# DC24V.net
KiCad netlist of a schematic drawn in Altium Designer
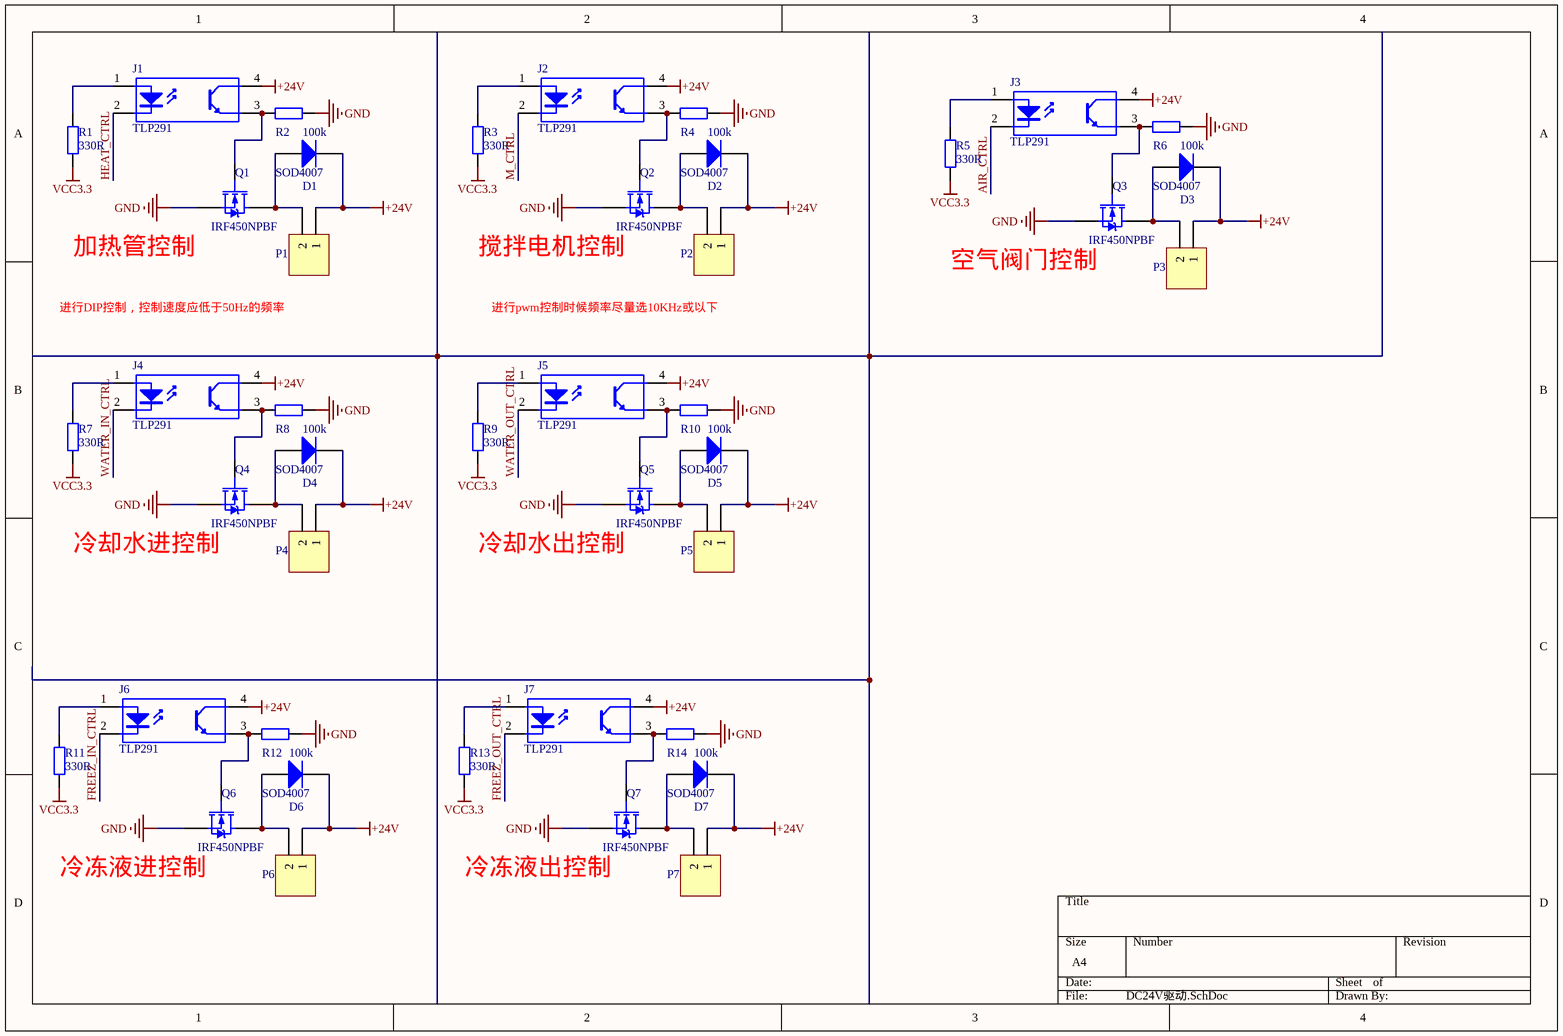
[diagram p0: DC24V驱动.SchDoc]

(export (version "E")
  (design (tool "Eeschema 10.0.6"))
  (components
    (comp (ref "D1")
      (value "Diode")
      (footprint "SOD123")
      (description "二极管")
      (fields (field (name "TYPE") "SOD4007") (field (name "PUBLISHER") "Altium Limited"))
      (libsource (lib "Fszhang") (part "Diode"))
    )
    (comp (ref "D2")
      (value "Diode")
      (footprint "SOD123")
      (description "二极管")
      (fields (field (name "TYPE") "SOD4007") (field (name "PUBLISHER") "Altium Limited"))
      (libsource (lib "Fszhang") (part "Diode"))
    )
    (comp (ref "D3")
      (value "Diode")
      (footprint "SOD123")
      (description "二极管")
      (fields (field (name "TYPE") "SOD4007") (field (name "PUBLISHER") "Altium Limited"))
      (libsource (lib "Fszhang") (part "Diode"))
    )
    (comp (ref "D4")
      (value "Diode")
      (footprint "SOD123")
      (description "二极管")
      (fields (field (name "TYPE") "SOD4007") (field (name "PUBLISHER") "Altium Limited"))
      (libsource (lib "Fszhang") (part "Diode"))
    )
    (comp (ref "D5")
      (value "Diode")
      (footprint "SOD123")
      (description "二极管")
      (fields (field (name "TYPE") "SOD4007") (field (name "PUBLISHER") "Altium Limited"))
      (libsource (lib "Fszhang") (part "Diode"))
    )
    (comp (ref "D6")
      (value "Diode")
      (footprint "SOD123")
      (description "二极管")
      (fields (field (name "TYPE") "SOD4007") (field (name "PUBLISHER") "Altium Limited"))
      (libsource (lib "Fszhang") (part "Diode"))
    )
    (comp (ref "D7")
      (value "Diode")
      (footprint "SOD123")
      (description "二极管")
      (fields (field (name "TYPE") "SOD4007") (field (name "PUBLISHER") "Altium Limited"))
      (libsource (lib "Fszhang") (part "Diode"))
    )
    (comp (ref "J1")
      (value "TLP291")
      (footprint "SOP127P710X350-4N")
      (description "光耦")
      (fields (field (name "PUBLISHER") "Altium Limited"))
      (libsource (lib "Fszhang") (part "TLP281"))
    )
    (comp (ref "J2")
      (value "TLP291")
      (footprint "SOP127P710X350-4N")
      (description "光耦")
      (fields (field (name "PUBLISHER") "Altium Limited"))
      (libsource (lib "Fszhang") (part "TLP281"))
    )
    (comp (ref "J3")
      (value "TLP291")
      (footprint "SOP127P710X350-4N")
      (description "光耦")
      (fields (field (name "PUBLISHER") "Altium Limited"))
      (libsource (lib "Fszhang") (part "TLP281"))
    )
    (comp (ref "J4")
      (value "TLP291")
      (footprint "SOP127P710X350-4N")
      (description "光耦")
      (fields (field (name "PUBLISHER") "Altium Limited"))
      (libsource (lib "Fszhang") (part "TLP281"))
    )
    (comp (ref "J5")
      (value "TLP291")
      (footprint "SOP127P710X350-4N")
      (description "光耦")
      (fields (field (name "PUBLISHER") "Altium Limited"))
      (libsource (lib "Fszhang") (part "TLP281"))
    )
    (comp (ref "J6")
      (value "TLP291")
      (footprint "SOP127P710X350-4N")
      (description "光耦")
      (fields (field (name "PUBLISHER") "Altium Limited"))
      (libsource (lib "Fszhang") (part "TLP281"))
    )
    (comp (ref "J7")
      (value "TLP291")
      (footprint "SOP127P710X350-4N")
      (description "光耦")
      (fields (field (name "PUBLISHER") "Altium Limited"))
      (libsource (lib "Fszhang") (part "TLP281"))
    )
    (comp (ref "P1")
      (value "Header 2")
      (footprint "HDR2X1_A")
      (description "接插件")
      (fields (field (name "PUBLISHER") "Altium Limited"))
      (libsource (lib "Fszhang") (part "Header 2"))
    )
    (comp (ref "P2")
      (value "Header 2")
      (footprint "HDR2X1_A")
      (description "接插件")
      (fields (field (name "PUBLISHER") "Altium Limited"))
      (libsource (lib "Fszhang") (part "Header 2"))
    )
    (comp (ref "P3")
      (value "Header 2")
      (footprint "HDR2X1_A")
      (description "接插件")
      (fields (field (name "PUBLISHER") "Altium Limited"))
      (libsource (lib "Fszhang") (part "Header 2"))
    )
    (comp (ref "P4")
      (value "Header 2")
      (footprint "HDR2X1_A")
      (description "接插件")
      (fields (field (name "PUBLISHER") "Altium Limited"))
      (libsource (lib "Fszhang") (part "Header 2"))
    )
    (comp (ref "P5")
      (value "Header 2")
      (footprint "HDR2X1_A")
      (description "接插件")
      (fields (field (name "PUBLISHER") "Altium Limited"))
      (libsource (lib "Fszhang") (part "Header 2"))
    )
    (comp (ref "P6")
      (value "Header 2")
      (footprint "HDR2X1_A")
      (description "接插件")
      (fields (field (name "PUBLISHER") "Altium Limited"))
      (libsource (lib "Fszhang") (part "Header 2"))
    )
    (comp (ref "P7")
      (value "Header 2")
      (footprint "HDR2X1_A")
      (description "接插件")
      (fields (field (name "PUBLISHER") "Altium Limited"))
      (libsource (lib "Fszhang") (part "Header 2"))
    )
    (comp (ref "Q1")
      (value "IRF450NPBF")
      (footprint "TO-263-2")
      (description "N-Channel MOSFET")
      (fields (field (name "PUBLISHER") "Altium Limited"))
      (libsource (lib "Fszhang") (part "MOSFET-N"))
    )
    (comp (ref "Q2")
      (value "IRF450NPBF")
      (footprint "TO-263-2")
      (description "N-Channel MOSFET")
      (fields (field (name "PUBLISHER") "Altium Limited"))
      (libsource (lib "Fszhang") (part "MOSFET-N"))
    )
    (comp (ref "Q3")
      (value "IRF450NPBF")
      (footprint "TO-263-2")
      (description "N-Channel MOSFET")
      (fields (field (name "PUBLISHER") "Altium Limited"))
      (libsource (lib "Fszhang") (part "MOSFET-N"))
    )
    (comp (ref "Q4")
      (value "IRF450NPBF")
      (footprint "TO-263-2")
      (description "N-Channel MOSFET")
      (fields (field (name "PUBLISHER") "Altium Limited"))
      (libsource (lib "Fszhang") (part "MOSFET-N"))
    )
    (comp (ref "Q5")
      (value "IRF450NPBF")
      (footprint "TO-263-2")
      (description "N-Channel MOSFET")
      (fields (field (name "PUBLISHER") "Altium Limited"))
      (libsource (lib "Fszhang") (part "MOSFET-N"))
    )
    (comp (ref "Q6")
      (value "IRF450NPBF")
      (footprint "TO-263-2")
      (description "N-Channel MOSFET")
      (fields (field (name "PUBLISHER") "Altium Limited"))
      (libsource (lib "Fszhang") (part "MOSFET-N"))
    )
    (comp (ref "Q7")
      (value "IRF450NPBF")
      (footprint "TO-263-2")
      (description "N-Channel MOSFET")
      (fields (field (name "PUBLISHER") "Altium Limited"))
      (libsource (lib "Fszhang") (part "MOSFET-N"))
    )
    (comp (ref "R1")
      (value "330R")
      (footprint "0603-1")
      (description "贴片电阻")
      (fields (field (name "Comment") "Res1") (field (name "PUBLISHER") "Altium Limited"))
      (libsource (lib "Fszhang") (part "Res1"))
    )
    (comp (ref "R2")
      (value "100k")
      (footprint "0603-1")
      (description "贴片电阻")
      (fields (field (name "Comment") "Res1") (field (name "PUBLISHER") "Altium Limited"))
      (libsource (lib "") (part "Res1_1"))
    )
    (comp (ref "R3")
      (value "330R")
      (footprint "0603-1")
      (description "贴片电阻")
      (fields (field (name "Comment") "Res1") (field (name "PUBLISHER") "Altium Limited"))
      (libsource (lib "Fszhang") (part "Res1"))
    )
    (comp (ref "R4")
      (value "100k")
      (footprint "0603-1")
      (description "贴片电阻")
      (fields (field (name "Comment") "Res1") (field (name "PUBLISHER") "Altium Limited"))
      (libsource (lib "") (part "Res1_1"))
    )
    (comp (ref "R5")
      (value "330R")
      (footprint "0603-1")
      (description "贴片电阻")
      (fields (field (name "Comment") "Res1") (field (name "PUBLISHER") "Altium Limited"))
      (libsource (lib "Fszhang") (part "Res1"))
    )
    (comp (ref "R6")
      (value "100k")
      (footprint "0603-1")
      (description "贴片电阻")
      (fields (field (name "Comment") "Res1") (field (name "PUBLISHER") "Altium Limited"))
      (libsource (lib "") (part "Res1_1"))
    )
    (comp (ref "R7")
      (value "330R")
      (footprint "0603-1")
      (description "贴片电阻")
      (fields (field (name "Comment") "Res1") (field (name "PUBLISHER") "Altium Limited"))
      (libsource (lib "Fszhang") (part "Res1"))
    )
    (comp (ref "R8")
      (value "100k")
      (footprint "0603-1")
      (description "贴片电阻")
      (fields (field (name "Comment") "Res1") (field (name "PUBLISHER") "Altium Limited"))
      (libsource (lib "") (part "Res1_1"))
    )
    (comp (ref "R9")
      (value "330R")
      (footprint "0603-1")
      (description "贴片电阻")
      (fields (field (name "Comment") "Res1") (field (name "PUBLISHER") "Altium Limited"))
      (libsource (lib "Fszhang") (part "Res1"))
    )
    (comp (ref "R10")
      (value "100k")
      (footprint "0603-1")
      (description "贴片电阻")
      (fields (field (name "Comment") "Res1") (field (name "PUBLISHER") "Altium Limited"))
      (libsource (lib "") (part "Res1_1"))
    )
    (comp (ref "R11")
      (value "330R")
      (footprint "0603-1")
      (description "贴片电阻")
      (fields (field (name "Comment") "Res1") (field (name "PUBLISHER") "Altium Limited"))
      (libsource (lib "Fszhang") (part "Res1"))
    )
    (comp (ref "R12")
      (value "100k")
      (footprint "0603-1")
      (description "贴片电阻")
      (fields (field (name "Comment") "Res1") (field (name "PUBLISHER") "Altium Limited"))
      (libsource (lib "") (part "Res1_1"))
    )
    (comp (ref "R13")
      (value "330R")
      (footprint "0603-1")
      (description "贴片电阻")
      (fields (field (name "Comment") "Res1") (field (name "PUBLISHER") "Altium Limited"))
      (libsource (lib "Fszhang") (part "Res1"))
    )
    (comp (ref "R14")
      (value "100k")
      (footprint "0603-1")
      (description "贴片电阻")
      (fields (field (name "Comment") "Res1") (field (name "PUBLISHER") "Altium Limited"))
      (libsource (lib "") (part "Res1_1"))
    )
  )
  (nets
    (net (code "1") (name "+24V") (class "Default")
      (node (ref "D1") (pin "2") (pinfunction "K_2") (pintype "passive"))
      (node (ref "D2") (pin "2") (pinfunction "K_2") (pintype "passive"))
      (node (ref "D3") (pin "2") (pinfunction "K_2") (pintype "passive"))
      (node (ref "D4") (pin "2") (pinfunction "K_2") (pintype "passive"))
      (node (ref "D5") (pin "2") (pinfunction "K_2") (pintype "passive"))
      (node (ref "D6") (pin "2") (pinfunction "K_2") (pintype "passive"))
      (node (ref "D7") (pin "2") (pinfunction "K_2") (pintype "passive"))
      (node (ref "J1") (pin "4") (pinfunction "C_4") (pintype "passive"))
      (node (ref "J2") (pin "4") (pinfunction "C_4") (pintype "passive"))
      (node (ref "J3") (pin "4") (pinfunction "C_4") (pintype "passive"))
      (node (ref "J4") (pin "4") (pinfunction "C_4") (pintype "passive"))
      (node (ref "J5") (pin "4") (pinfunction "C_4") (pintype "passive"))
      (node (ref "J6") (pin "4") (pinfunction "C_4") (pintype "passive"))
      (node (ref "J7") (pin "4") (pinfunction "C_4") (pintype "passive"))
      (node (ref "P1") (pin "1") (pinfunction "1_1") (pintype "passive"))
      (node (ref "P2") (pin "1") (pinfunction "1_1") (pintype "passive"))
      (node (ref "P3") (pin "1") (pinfunction "1_1") (pintype "passive"))
      (node (ref "P4") (pin "1") (pinfunction "1_1") (pintype "passive"))
      (node (ref "P5") (pin "1") (pinfunction "1_1") (pintype "passive"))
      (node (ref "P6") (pin "1") (pinfunction "1_1") (pintype "passive"))
      (node (ref "P7") (pin "1") (pinfunction "1_1") (pintype "passive"))
    )
    (net (code "2") (name "/AIR_CTRL") (class "Default")
      (node (ref "J3") (pin "2") (pinfunction "K_2") (pintype "passive"))
    )
    (net (code "3") (name "/FREEZ_IN_CTRL") (class "Default")
      (node (ref "J6") (pin "2") (pinfunction "K_2") (pintype "passive"))
    )
    (net (code "4") (name "/FREEZ_OUT_CTRL") (class "Default")
      (node (ref "J7") (pin "2") (pinfunction "K_2") (pintype "passive"))
    )
    (net (code "5") (name "/HEAT_CTRL") (class "Default")
      (node (ref "J1") (pin "2") (pinfunction "K_2") (pintype "passive"))
    )
    (net (code "6") (name "/M_CTRL") (class "Default")
      (node (ref "J2") (pin "2") (pinfunction "K_2") (pintype "passive"))
    )
    (net (code "7") (name "/WATER_IN_CTRL") (class "Default")
      (node (ref "J4") (pin "2") (pinfunction "K_2") (pintype "passive"))
    )
    (net (code "8") (name "/WATER_OUT_CTRL") (class "Default")
      (node (ref "J5") (pin "2") (pinfunction "K_2") (pintype "passive"))
    )
    (net (code "9") (name "GND") (class "Default")
      (node (ref "Q1") (pin "2") (pinfunction "S_2") (pintype "passive"))
      (node (ref "Q2") (pin "2") (pinfunction "S_2") (pintype "passive"))
      (node (ref "Q3") (pin "2") (pinfunction "S_2") (pintype "passive"))
      (node (ref "Q4") (pin "2") (pinfunction "S_2") (pintype "passive"))
      (node (ref "Q5") (pin "2") (pinfunction "S_2") (pintype "passive"))
      (node (ref "Q6") (pin "2") (pinfunction "S_2") (pintype "passive"))
      (node (ref "Q7") (pin "2") (pinfunction "S_2") (pintype "passive"))
      (node (ref "R10") (pin "1") (pinfunction "1_1") (pintype "passive"))
      (node (ref "R12") (pin "1") (pinfunction "1_1") (pintype "passive"))
      (node (ref "R14") (pin "1") (pinfunction "1_1") (pintype "passive"))
      (node (ref "R2") (pin "1") (pinfunction "1_1") (pintype "passive"))
      (node (ref "R4") (pin "1") (pinfunction "1_1") (pintype "passive"))
      (node (ref "R6") (pin "1") (pinfunction "1_1") (pintype "passive"))
      (node (ref "R8") (pin "1") (pinfunction "1_1") (pintype "passive"))
    )
    (net (code "10") (name "Net-(D1-A)") (class "Default")
      (node (ref "D1") (pin "1") (pinfunction "A_1") (pintype "passive"))
      (node (ref "P1") (pin "2") (pinfunction "2_2") (pintype "passive"))
      (node (ref "Q1") (pin "3") (pinfunction "D_3") (pintype "passive"))
    )
    (net (code "11") (name "Net-(D2-A)") (class "Default")
      (node (ref "D2") (pin "1") (pinfunction "A_1") (pintype "passive"))
      (node (ref "P2") (pin "2") (pinfunction "2_2") (pintype "passive"))
      (node (ref "Q2") (pin "3") (pinfunction "D_3") (pintype "passive"))
    )
    (net (code "12") (name "Net-(D3-A)") (class "Default")
      (node (ref "D3") (pin "1") (pinfunction "A_1") (pintype "passive"))
      (node (ref "P3") (pin "2") (pinfunction "2_2") (pintype "passive"))
      (node (ref "Q3") (pin "3") (pinfunction "D_3") (pintype "passive"))
    )
    (net (code "13") (name "Net-(D4-A)") (class "Default")
      (node (ref "D4") (pin "1") (pinfunction "A_1") (pintype "passive"))
      (node (ref "P4") (pin "2") (pinfunction "2_2") (pintype "passive"))
      (node (ref "Q4") (pin "3") (pinfunction "D_3") (pintype "passive"))
    )
    (net (code "14") (name "Net-(D5-A)") (class "Default")
      (node (ref "D5") (pin "1") (pinfunction "A_1") (pintype "passive"))
      (node (ref "P5") (pin "2") (pinfunction "2_2") (pintype "passive"))
      (node (ref "Q5") (pin "3") (pinfunction "D_3") (pintype "passive"))
    )
    (net (code "15") (name "Net-(D6-A)") (class "Default")
      (node (ref "D6") (pin "1") (pinfunction "A_1") (pintype "passive"))
      (node (ref "P6") (pin "2") (pinfunction "2_2") (pintype "passive"))
      (node (ref "Q6") (pin "3") (pinfunction "D_3") (pintype "passive"))
    )
    (net (code "16") (name "Net-(D7-A)") (class "Default")
      (node (ref "D7") (pin "1") (pinfunction "A_1") (pintype "passive"))
      (node (ref "P7") (pin "2") (pinfunction "2_2") (pintype "passive"))
      (node (ref "Q7") (pin "3") (pinfunction "D_3") (pintype "passive"))
    )
    (net (code "17") (name "Net-(J1-A)") (class "Default")
      (node (ref "J1") (pin "1") (pinfunction "A_1") (pintype "passive"))
      (node (ref "R1") (pin "1") (pinfunction "1_1") (pintype "passive"))
    )
    (net (code "18") (name "Net-(J1-E)") (class "Default")
      (node (ref "J1") (pin "3") (pinfunction "E_3") (pintype "passive"))
      (node (ref "Q1") (pin "1") (pinfunction "G_1") (pintype "passive"))
      (node (ref "R2") (pin "2") (pinfunction "2_2") (pintype "passive"))
    )
    (net (code "19") (name "Net-(J2-A)") (class "Default")
      (node (ref "J2") (pin "1") (pinfunction "A_1") (pintype "passive"))
      (node (ref "R3") (pin "1") (pinfunction "1_1") (pintype "passive"))
    )
    (net (code "20") (name "Net-(J2-E)") (class "Default")
      (node (ref "J2") (pin "3") (pinfunction "E_3") (pintype "passive"))
      (node (ref "Q2") (pin "1") (pinfunction "G_1") (pintype "passive"))
      (node (ref "R4") (pin "2") (pinfunction "2_2") (pintype "passive"))
    )
    (net (code "21") (name "Net-(J3-A)") (class "Default")
      (node (ref "J3") (pin "1") (pinfunction "A_1") (pintype "passive"))
      (node (ref "R5") (pin "1") (pinfunction "1_1") (pintype "passive"))
    )
    (net (code "22") (name "Net-(J3-E)") (class "Default")
      (node (ref "J3") (pin "3") (pinfunction "E_3") (pintype "passive"))
      (node (ref "Q3") (pin "1") (pinfunction "G_1") (pintype "passive"))
      (node (ref "R6") (pin "2") (pinfunction "2_2") (pintype "passive"))
    )
    (net (code "23") (name "Net-(J4-A)") (class "Default")
      (node (ref "J4") (pin "1") (pinfunction "A_1") (pintype "passive"))
      (node (ref "R7") (pin "1") (pinfunction "1_1") (pintype "passive"))
    )
    (net (code "24") (name "Net-(J4-E)") (class "Default")
      (node (ref "J4") (pin "3") (pinfunction "E_3") (pintype "passive"))
      (node (ref "Q4") (pin "1") (pinfunction "G_1") (pintype "passive"))
      (node (ref "R8") (pin "2") (pinfunction "2_2") (pintype "passive"))
    )
    (net (code "25") (name "Net-(J5-A)") (class "Default")
      (node (ref "J5") (pin "1") (pinfunction "A_1") (pintype "passive"))
      (node (ref "R9") (pin "1") (pinfunction "1_1") (pintype "passive"))
    )
    (net (code "26") (name "Net-(J5-E)") (class "Default")
      (node (ref "J5") (pin "3") (pinfunction "E_3") (pintype "passive"))
      (node (ref "Q5") (pin "1") (pinfunction "G_1") (pintype "passive"))
      (node (ref "R10") (pin "2") (pinfunction "2_2") (pintype "passive"))
    )
    (net (code "27") (name "Net-(J6-A)") (class "Default")
      (node (ref "J6") (pin "1") (pinfunction "A_1") (pintype "passive"))
      (node (ref "R11") (pin "1") (pinfunction "1_1") (pintype "passive"))
    )
    (net (code "28") (name "Net-(J6-E)") (class "Default")
      (node (ref "J6") (pin "3") (pinfunction "E_3") (pintype "passive"))
      (node (ref "Q6") (pin "1") (pinfunction "G_1") (pintype "passive"))
      (node (ref "R12") (pin "2") (pinfunction "2_2") (pintype "passive"))
    )
    (net (code "29") (name "Net-(J7-A)") (class "Default")
      (node (ref "J7") (pin "1") (pinfunction "A_1") (pintype "passive"))
      (node (ref "R13") (pin "1") (pinfunction "1_1") (pintype "passive"))
    )
    (net (code "30") (name "Net-(J7-E)") (class "Default")
      (node (ref "J7") (pin "3") (pinfunction "E_3") (pintype "passive"))
      (node (ref "Q7") (pin "1") (pinfunction "G_1") (pintype "passive"))
      (node (ref "R14") (pin "2") (pinfunction "2_2") (pintype "passive"))
    )
    (net (code "31") (name "VCC3.3") (class "Default")
      (node (ref "R1") (pin "2") (pinfunction "2_2") (pintype "passive"))
      (node (ref "R11") (pin "2") (pinfunction "2_2") (pintype "passive"))
      (node (ref "R13") (pin "2") (pinfunction "2_2") (pintype "passive"))
      (node (ref "R3") (pin "2") (pinfunction "2_2") (pintype "passive"))
      (node (ref "R5") (pin "2") (pinfunction "2_2") (pintype "passive"))
      (node (ref "R7") (pin "2") (pinfunction "2_2") (pintype "passive"))
      (node (ref "R9") (pin "2") (pinfunction "2_2") (pintype "passive"))
    )
  )
)
